# TestAdapter_02.net
KiCad netlist of a schematic drawn in EAGLE
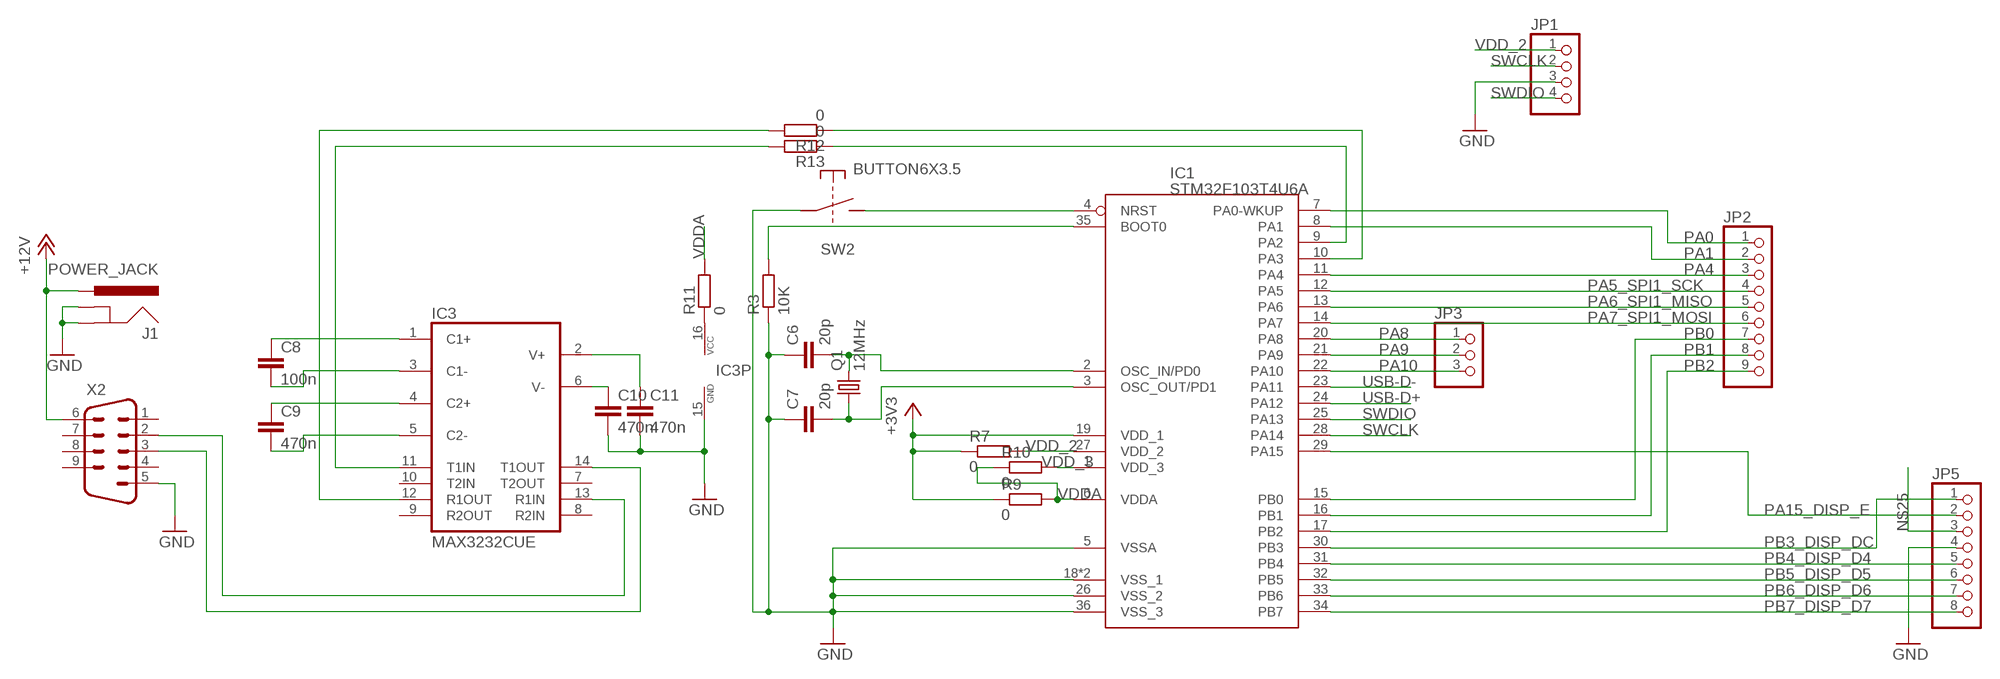
[diagram p0: schematic, sheet 1]
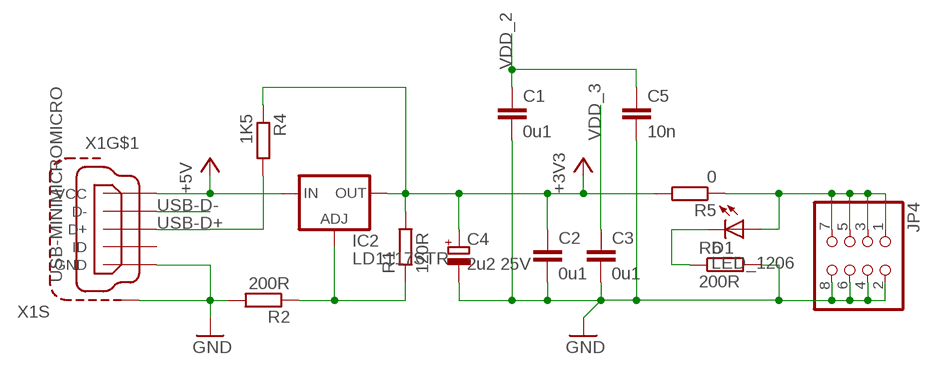
[diagram p1: schematic, sheet 2]

(export (version "E")
  (design (tool "Eeschema 10.0.6"))
  (components
    (comp (ref "C1")
      (value "0u1")
      (footprint "eagle-import:CAP0805")
      (libsource (lib "eagle-import") (part "CAP_0805"))
    )
    (comp (ref "C2")
      (value "0u1")
      (footprint "eagle-import:CAP0805")
      (libsource (lib "eagle-import") (part "CAP_0805"))
    )
    (comp (ref "C3")
      (value "0u1")
      (footprint "eagle-import:CAP0805")
      (libsource (lib "eagle-import") (part "CAP_0805"))
    )
    (comp (ref "C4")
      (value "2u2 25V")
      (footprint "eagle-import:CAPMP3317X180")
      (libsource (lib "eagle-import") (part "CAP-POL_CAPE3216-A"))
    )
    (comp (ref "C5")
      (value "10n")
      (footprint "eagle-import:CAP0805")
      (libsource (lib "eagle-import") (part "CAP_0805"))
    )
    (comp (ref "D1")
      (value "LED_1206")
      (footprint "eagle-import:LED1206")
      (libsource (lib "eagle-import") (part "LED_1206"))
    )
    (comp (ref "IC2")
      (value "LD1117STR")
      (footprint "eagle-import:SOT230P700X180-4")
      (libsource (lib "eagle-import") (part "VREG-ADJLD1117S"))
    )
    (comp (ref "JP4")
      (value "PINHD-2X4")
      (footprint "eagle-import:2X04")
      (libsource (lib "eagle-import") (part "PINHD-2X4"))
    )
    (comp (ref "R1")
      (value "120R")
      (footprint "eagle-import:RESC2012X50")
      (libsource (lib "eagle-import") (part "R_R0805"))
    )
    (comp (ref "R2")
      (value "200R")
      (footprint "eagle-import:RESC2012X50")
      (libsource (lib "eagle-import") (part "R_R0805"))
    )
    (comp (ref "R4")
      (value "1K5")
      (footprint "eagle-import:RESC2012X50")
      (libsource (lib "eagle-import") (part "R_R0805"))
    )
    (comp (ref "R5")
      (value "0")
      (footprint "eagle-import:RESC2012X50")
      (libsource (lib "eagle-import") (part "R_R0805"))
    )
    (comp (ref "R6")
      (value "200R")
      (footprint "eagle-import:RESC2012X50")
      (libsource (lib "eagle-import") (part "R_R0805"))
    )
    (comp (ref "X1")
      (value "USB-MINIMICROMICRO")
      (footprint "eagle-import:USB-B-MICRO-SMD")
      (libsource (lib "eagle-import") (part "USB-MINIMICROMICRO"))
    )
    (comp (ref "C6")
      (value "20p")
      (footprint "eagle-import:CAP0805")
      (libsource (lib "eagle-import") (part "CAP_0805"))
    )
    (comp (ref "C7")
      (value "20p")
      (footprint "eagle-import:CAP0805")
      (libsource (lib "eagle-import") (part "CAP_0805"))
    )
    (comp (ref "C8")
      (value "100n")
      (footprint "eagle-import:CAP0805")
      (libsource (lib "eagle-import") (part "CAP_0805"))
    )
    (comp (ref "C9")
      (value "470n")
      (footprint "eagle-import:CAP0805")
      (libsource (lib "eagle-import") (part "CAP_0805"))
    )
    (comp (ref "C10")
      (value "470n")
      (footprint "eagle-import:CAP0805")
      (libsource (lib "eagle-import") (part "CAP_0805"))
    )
    (comp (ref "C11")
      (value "470n")
      (footprint "eagle-import:CAP0805")
      (libsource (lib "eagle-import") (part "CAP_0805"))
    )
    (comp (ref "IC1")
      (value "STM32F103T4U6A")
      (footprint "eagle-import:QFN50P606X606X100-36")
      (libsource (lib "eagle-import") (part "STM32F103T4U6A"))
    )
    (comp (ref "IC3")
      (value "MAX3232CUE")
      (footprint "eagle-import:TSSOP16")
      (fields (field (name "MF") "MAXIM") (field (name "MPN") "MAX3232CUE+"))
      (libsource (lib "eagle-import") (part "MAX3232UEC"))
    )
    (comp (ref "J1")
      (value "POWER_JACK")
      (footprint "eagle-import:POWER_JACK_PTH")
      (libsource (lib "eagle-import") (part "POWER_JACK"))
    )
    (comp (ref "JP1")
      (value "PINHD-1X4")
      (footprint "eagle-import:1X04")
      (libsource (lib "eagle-import") (part "PINHD-1X4"))
    )
    (comp (ref "JP2")
      (value "PINHD-1X9")
      (footprint "eagle-import:1X09")
      (libsource (lib "eagle-import") (part "PINHD-1X9"))
    )
    (comp (ref "JP3")
      (value "PINHD-1X3")
      (footprint "eagle-import:1X03")
      (libsource (lib "eagle-import") (part "PINHD-1X3"))
    )
    (comp (ref "JP5")
      (value "PINHD-1X8")
      (footprint "eagle-import:1X08")
      (libsource (lib "eagle-import") (part "PINHD-1X8"))
    )
    (comp (ref "Q1")
      (value "12MHz")
      (footprint "eagle-import:CRYSTAL-5025")
      (libsource (lib "eagle-import") (part "CRYSTAL5032"))
    )
    (comp (ref "R3")
      (value "10K")
      (footprint "eagle-import:RESC2012X50")
      (libsource (lib "eagle-import") (part "R_R0805"))
    )
    (comp (ref "R7")
      (value "0")
      (footprint "eagle-import:RESC2012X50")
      (libsource (lib "eagle-import") (part "R_R0805"))
    )
    (comp (ref "R9")
      (value "0")
      (footprint "eagle-import:RESC2012X50")
      (libsource (lib "eagle-import") (part "R_R0805"))
    )
    (comp (ref "R10")
      (value "0")
      (footprint "eagle-import:RESC2012X50")
      (libsource (lib "eagle-import") (part "R_R0805"))
    )
    (comp (ref "R11")
      (value "0")
      (footprint "eagle-import:RESC2012X50")
      (libsource (lib "eagle-import") (part "R_R0805"))
    )
    (comp (ref "R12")
      (value "0")
      (footprint "eagle-import:RESC2012X50")
      (libsource (lib "eagle-import") (part "R_R0805"))
    )
    (comp (ref "R13")
      (value "0")
      (footprint "eagle-import:RESC2012X50")
      (libsource (lib "eagle-import") (part "R_R0805"))
    )
    (comp (ref "SW2")
      (value "BUTTON6X3.5")
      (footprint "eagle-import:SW-6X3.5")
      (libsource (lib "eagle-import") (part "BUTTON6X3.5"))
    )
    (comp (ref "X2")
      (value "M09-182")
      (footprint "eagle-import:182-009-MALE")
      (libsource (lib "eagle-import") (part "M09-182"))
    )
  )
  (nets
    (net (code "1") (name "+3V3") (class "Default")
      (node (ref "C2") (pin "1") (pinfunction "1_1") (pintype "passive"))
      (node (ref "C4") (pin "1") (pinfunction "+_1") (pintype "passive"))
      (node (ref "IC1") (pin "19") (pinfunction "VDD_1_19") (pintype "power_in"))
      (node (ref "IC2") (pin "2") (pinfunction "OUT_2") (pintype "passive"))
      (node (ref "IC2") (pin "4") (pinfunction "OUT_4") (pintype "passive"))
      (node (ref "R1") (pin "2") (pinfunction "2_2") (pintype "passive"))
      (node (ref "R4") (pin "1") (pinfunction "1_1") (pintype "passive"))
      (node (ref "R5") (pin "2") (pinfunction "2_2") (pintype "passive"))
      (node (ref "R7") (pin "1") (pinfunction "1_1") (pintype "passive"))
      (node (ref "R9") (pin "1") (pinfunction "1_1") (pintype "passive"))
    )
    (net (code "2") (name "+5V") (class "Default")
      (node (ref "IC2") (pin "3") (pinfunction "IN_3") (pintype "input"))
      (node (ref "X1") (pin "VBUS") (pinfunction "VCC_VBUS") (pintype "passive"))
    )
    (net (code "3") (name "+12V") (class "Default")
      (node (ref "J1") (pin "PWR") (pinfunction "PWR_PWR") (pintype "bidirectional"))
      (node (ref "X2") (pin "6") (pinfunction "6_6") (pintype "passive"))
    )
    (net (code "4") (name "GND") (class "Default")
      (node (ref "C1") (pin "2") (pinfunction "2_2") (pintype "passive"))
      (node (ref "C10") (pin "2") (pinfunction "2_2") (pintype "passive"))
      (node (ref "C11") (pin "2") (pinfunction "2_2") (pintype "passive"))
      (node (ref "C2") (pin "2") (pinfunction "2_2") (pintype "passive"))
      (node (ref "C3") (pin "2") (pinfunction "2_2") (pintype "passive"))
      (node (ref "C4") (pin "2") (pinfunction "-_2") (pintype "passive"))
      (node (ref "C5") (pin "2") (pinfunction "2_2") (pintype "passive"))
      (node (ref "C6") (pin "1") (pinfunction "1_1") (pintype "passive"))
      (node (ref "C7") (pin "1") (pinfunction "1_1") (pintype "passive"))
      (node (ref "IC1") (pin "18") (pinfunction "VSS_1_18") (pintype "power_in"))
      (node (ref "IC1") (pin "26") (pinfunction "VSS_2_26") (pintype "power_in"))
      (node (ref "IC1") (pin "36") (pinfunction "VSS_3_36") (pintype "power_in"))
      (node (ref "IC1") (pin "5") (pinfunction "VSSA_5") (pintype "power_in"))
      (node (ref "IC1") (pin "P$1") (pinfunction "VSS_1_P$1") (pintype "power_in"))
      (node (ref "IC3") (pin "15") (pinfunction "GND_15") (pintype "power_in"))
      (node (ref "J1") (pin "GND") (pinfunction "GND_GND") (pintype "bidirectional"))
      (node (ref "J1") (pin "GNDBREAK") (pinfunction "GNDBREAK_GNDBREAK") (pintype "bidirectional"))
      (node (ref "JP1") (pin "3") (pinfunction "3_3") (pintype "passive"))
      (node (ref "JP4") (pin "2") (pinfunction "2_2") (pintype "passive"))
      (node (ref "JP4") (pin "4") (pinfunction "4_4") (pintype "passive"))
      (node (ref "JP4") (pin "6") (pinfunction "6_6") (pintype "passive"))
      (node (ref "JP4") (pin "8") (pinfunction "8_8") (pintype "passive"))
      (node (ref "JP5") (pin "4") (pinfunction "4_4") (pintype "passive"))
      (node (ref "R2") (pin "2") (pinfunction "2_2") (pintype "passive"))
      (node (ref "R3") (pin "1") (pinfunction "1_1") (pintype "passive"))
      (node (ref "R6") (pin "2") (pinfunction "2_2") (pintype "passive"))
      (node (ref "SW2") (pin "1") (pinfunction "1_1") (pintype "passive"))
      (node (ref "X1") (pin "GND") (pinfunction "GND_GND") (pintype "passive"))
      (node (ref "X1") (pin "SHIELD1") (pinfunction "S1_SHIELD1") (pintype "passive"))
      (node (ref "X1") (pin "SHIELD2") (pinfunction "S1_SHIELD2") (pintype "passive"))
      (node (ref "X1") (pin "SHIELD3") (pinfunction "S1_SHIELD3") (pintype "passive"))
      (node (ref "X2") (pin "5") (pinfunction "5_5") (pintype "passive"))
    )
    (net (code "5") (name "N$25") (class "Default")
      (node (ref "D1") (pin "A") (pinfunction "A_A") (pintype "passive"))
      (node (ref "JP4") (pin "1") (pinfunction "1_1") (pintype "passive"))
      (node (ref "JP4") (pin "3") (pinfunction "3_3") (pintype "passive"))
      (node (ref "JP4") (pin "5") (pinfunction "5_5") (pintype "passive"))
      (node (ref "JP4") (pin "7") (pinfunction "7_7") (pintype "passive"))
      (node (ref "JP5") (pin "3") (pinfunction "3_3") (pintype "passive"))
      (node (ref "R5") (pin "1") (pinfunction "1_1") (pintype "passive"))
    )
    (net (code "6") (name "Net-(D1-PadC)") (class "Default")
      (node (ref "D1") (pin "C") (pinfunction "C_C") (pintype "passive"))
      (node (ref "R6") (pin "1") (pinfunction "1_1") (pintype "passive"))
    )
    (net (code "7") (name "Net-(IC1-BOOT0)") (class "Default")
      (node (ref "IC1") (pin "35") (pinfunction "BOOT0_35") (pintype "bidirectional"))
      (node (ref "R3") (pin "2") (pinfunction "2_2") (pintype "passive"))
    )
    (net (code "8") (name "Net-(IC1-NRST)") (class "Default")
      (node (ref "IC1") (pin "4") (pinfunction "NRST_4") (pintype "bidirectional"))
      (node (ref "SW2") (pin "2") (pinfunction "2_2") (pintype "passive"))
    )
    (net (code "9") (name "Net-(IC1-OSC_IN{slash}PD0)") (class "Default")
      (node (ref "C6") (pin "2") (pinfunction "2_2") (pintype "passive"))
      (node (ref "IC1") (pin "2") (pinfunction "OSC_IN/PD0_2") (pintype "bidirectional"))
      (node (ref "Q1") (pin "P$2") (pinfunction "2_P$2") (pintype "passive"))
    )
    (net (code "10") (name "Net-(IC1-OSC_OUT{slash}PD1)") (class "Default")
      (node (ref "C7") (pin "2") (pinfunction "2_2") (pintype "passive"))
      (node (ref "IC1") (pin "3") (pinfunction "OSC_OUT/PD1_3") (pintype "bidirectional"))
      (node (ref "Q1") (pin "P$1") (pinfunction "1_P$1") (pintype "passive"))
    )
    (net (code "11") (name "Net-(IC1-PA2)") (class "Default")
      (node (ref "IC1") (pin "9") (pinfunction "PA2_9") (pintype "bidirectional"))
      (node (ref "R13") (pin "1") (pinfunction "1_1") (pintype "passive"))
    )
    (net (code "12") (name "Net-(IC1-PA3)") (class "Default")
      (node (ref "IC1") (pin "10") (pinfunction "PA3_10") (pintype "bidirectional"))
      (node (ref "R12") (pin "1") (pinfunction "1_1") (pintype "passive"))
    )
    (net (code "13") (name "Net-(IC2-ADJ)") (class "Default")
      (node (ref "IC2") (pin "1") (pinfunction "ADJ_1") (pintype "input"))
      (node (ref "R1") (pin "1") (pinfunction "1_1") (pintype "passive"))
      (node (ref "R2") (pin "1") (pinfunction "1_1") (pintype "passive"))
    )
    (net (code "14") (name "Net-(IC3A-C1+)") (class "Default")
      (node (ref "C8") (pin "1") (pinfunction "1_1") (pintype "passive"))
      (node (ref "IC3") (pin "1") (pinfunction "C1+_1") (pintype "bidirectional"))
    )
    (net (code "15") (name "Net-(IC3A-C1-)") (class "Default")
      (node (ref "C8") (pin "2") (pinfunction "2_2") (pintype "passive"))
      (node (ref "IC3") (pin "3") (pinfunction "C1-_3") (pintype "bidirectional"))
    )
    (net (code "16") (name "Net-(IC3A-C2+)") (class "Default")
      (node (ref "C9") (pin "1") (pinfunction "1_1") (pintype "passive"))
      (node (ref "IC3") (pin "4") (pinfunction "C2+_4") (pintype "bidirectional"))
    )
    (net (code "17") (name "Net-(IC3A-C2-)") (class "Default")
      (node (ref "C9") (pin "2") (pinfunction "2_2") (pintype "passive"))
      (node (ref "IC3") (pin "5") (pinfunction "C2-_5") (pintype "bidirectional"))
    )
    (net (code "18") (name "Net-(IC3A-R1IN)") (class "Default")
      (node (ref "IC3") (pin "13") (pinfunction "R1IN_13") (pintype "input"))
      (node (ref "X2") (pin "2") (pinfunction "2_2") (pintype "passive"))
    )
    (net (code "19") (name "Net-(IC3A-R1OUT)") (class "Default")
      (node (ref "IC3") (pin "12") (pinfunction "R1OUT_12") (pintype "output"))
      (node (ref "R12") (pin "2") (pinfunction "2_2") (pintype "passive"))
    )
    (net (code "20") (name "Net-(IC3A-T1IN)") (class "Default")
      (node (ref "IC3") (pin "11") (pinfunction "T1IN_11") (pintype "input"))
      (node (ref "R13") (pin "2") (pinfunction "2_2") (pintype "passive"))
    )
    (net (code "21") (name "Net-(IC3A-T1OUT)") (class "Default")
      (node (ref "IC3") (pin "14") (pinfunction "T1OUT_14") (pintype "output"))
      (node (ref "X2") (pin "3") (pinfunction "3_3") (pintype "passive"))
    )
    (net (code "22") (name "Net-(IC3A-V+)") (class "Default")
      (node (ref "C11") (pin "1") (pinfunction "1_1") (pintype "passive"))
      (node (ref "IC3") (pin "2") (pinfunction "V+_2") (pintype "bidirectional"))
    )
    (net (code "23") (name "Net-(IC3A-V-)") (class "Default")
      (node (ref "C10") (pin "1") (pinfunction "1_1") (pintype "passive"))
      (node (ref "IC3") (pin "6") (pinfunction "V-_6") (pintype "bidirectional"))
    )
    (net (code "24") (name "Net-(IC3B-VCC)") (class "Default")
      (node (ref "IC3") (pin "16") (pinfunction "VCC_16") (pintype "power_in"))
      (node (ref "R11") (pin "1") (pinfunction "1_1") (pintype "passive"))
    )
    (net (code "25") (name "PA0") (class "Default")
      (node (ref "IC1") (pin "7") (pinfunction "PA0-WKUP_7") (pintype "bidirectional"))
      (node (ref "JP2") (pin "1") (pinfunction "1_1") (pintype "passive"))
    )
    (net (code "26") (name "PA1") (class "Default")
      (node (ref "IC1") (pin "8") (pinfunction "PA1_8") (pintype "bidirectional"))
      (node (ref "JP2") (pin "2") (pinfunction "2_2") (pintype "passive"))
    )
    (net (code "27") (name "PA4") (class "Default")
      (node (ref "IC1") (pin "11") (pinfunction "PA4_11") (pintype "bidirectional"))
      (node (ref "JP2") (pin "3") (pinfunction "3_3") (pintype "passive"))
    )
    (net (code "28") (name "PA5_SPI1_SCK") (class "Default")
      (node (ref "IC1") (pin "12") (pinfunction "PA5_12") (pintype "bidirectional"))
      (node (ref "JP2") (pin "4") (pinfunction "4_4") (pintype "passive"))
    )
    (net (code "29") (name "PA6_SPI1_MISO") (class "Default")
      (node (ref "IC1") (pin "13") (pinfunction "PA6_13") (pintype "bidirectional"))
      (node (ref "JP2") (pin "5") (pinfunction "5_5") (pintype "passive"))
    )
    (net (code "30") (name "PA7_SPI1_MOSI") (class "Default")
      (node (ref "IC1") (pin "14") (pinfunction "PA7_14") (pintype "bidirectional"))
      (node (ref "JP2") (pin "6") (pinfunction "6_6") (pintype "passive"))
    )
    (net (code "31") (name "PA8") (class "Default")
      (node (ref "IC1") (pin "20") (pinfunction "PA8_20") (pintype "bidirectional"))
      (node (ref "JP3") (pin "1") (pinfunction "1_1") (pintype "passive"))
    )
    (net (code "32") (name "PA9") (class "Default")
      (node (ref "IC1") (pin "21") (pinfunction "PA9_21") (pintype "bidirectional"))
      (node (ref "JP3") (pin "2") (pinfunction "2_2") (pintype "passive"))
    )
    (net (code "33") (name "PA10") (class "Default")
      (node (ref "IC1") (pin "22") (pinfunction "PA10_22") (pintype "bidirectional"))
      (node (ref "JP3") (pin "3") (pinfunction "3_3") (pintype "passive"))
    )
    (net (code "34") (name "PA15_DISP_E") (class "Default")
      (node (ref "IC1") (pin "29") (pinfunction "PA15_29") (pintype "bidirectional"))
      (node (ref "JP5") (pin "2") (pinfunction "2_2") (pintype "passive"))
    )
    (net (code "35") (name "PB0") (class "Default")
      (node (ref "IC1") (pin "15") (pinfunction "PB0_15") (pintype "bidirectional"))
      (node (ref "JP2") (pin "7") (pinfunction "7_7") (pintype "passive"))
    )
    (net (code "36") (name "PB1") (class "Default")
      (node (ref "IC1") (pin "16") (pinfunction "PB1_16") (pintype "bidirectional"))
      (node (ref "JP2") (pin "8") (pinfunction "8_8") (pintype "passive"))
    )
    (net (code "37") (name "PB2") (class "Default")
      (node (ref "IC1") (pin "17") (pinfunction "PB2_17") (pintype "bidirectional"))
      (node (ref "JP2") (pin "9") (pinfunction "9_9") (pintype "passive"))
    )
    (net (code "38") (name "PB3_DISP_DC") (class "Default")
      (node (ref "IC1") (pin "30") (pinfunction "PB3_30") (pintype "bidirectional"))
      (node (ref "JP5") (pin "1") (pinfunction "1_1") (pintype "passive"))
    )
    (net (code "39") (name "PB4_DISP_D4") (class "Default")
      (node (ref "IC1") (pin "31") (pinfunction "PB4_31") (pintype "bidirectional"))
      (node (ref "JP5") (pin "5") (pinfunction "5_5") (pintype "passive"))
    )
    (net (code "40") (name "PB5_DISP_D5") (class "Default")
      (node (ref "IC1") (pin "32") (pinfunction "PB5_32") (pintype "bidirectional"))
      (node (ref "JP5") (pin "6") (pinfunction "6_6") (pintype "passive"))
    )
    (net (code "41") (name "PB6_DISP_D6") (class "Default")
      (node (ref "IC1") (pin "33") (pinfunction "PB6_33") (pintype "bidirectional"))
      (node (ref "JP5") (pin "7") (pinfunction "7_7") (pintype "passive"))
    )
    (net (code "42") (name "PB7_DISP_D7") (class "Default")
      (node (ref "IC1") (pin "34") (pinfunction "PB7_34") (pintype "bidirectional"))
      (node (ref "JP5") (pin "8") (pinfunction "8_8") (pintype "passive"))
    )
    (net (code "43") (name "SWCLK") (class "Default")
      (node (ref "IC1") (pin "28") (pinfunction "PA14_28") (pintype "bidirectional"))
      (node (ref "JP1") (pin "2") (pinfunction "2_2") (pintype "passive"))
    )
    (net (code "44") (name "SWDIO") (class "Default")
      (node (ref "IC1") (pin "25") (pinfunction "PA13_25") (pintype "bidirectional"))
      (node (ref "JP1") (pin "4") (pinfunction "4_4") (pintype "passive"))
    )
    (net (code "45") (name "USB-D+") (class "Default")
      (node (ref "IC1") (pin "24") (pinfunction "PA12_24") (pintype "bidirectional"))
      (node (ref "R4") (pin "2") (pinfunction "2_2") (pintype "passive"))
      (node (ref "X1") (pin "D+") (pinfunction "D+_D+") (pintype "passive"))
    )
    (net (code "46") (name "USB-D-") (class "Default")
      (node (ref "IC1") (pin "23") (pinfunction "PA11_23") (pintype "bidirectional"))
      (node (ref "X1") (pin "D-") (pinfunction "D-_D-") (pintype "passive"))
    )
    (net (code "47") (name "VDDA") (class "Default")
      (node (ref "IC1") (pin "6") (pinfunction "VDDA_6") (pintype "power_in"))
      (node (ref "R10") (pin "1") (pinfunction "1_1") (pintype "passive"))
      (node (ref "R11") (pin "2") (pinfunction "2_2") (pintype "passive"))
      (node (ref "R9") (pin "2") (pinfunction "2_2") (pintype "passive"))
    )
    (net (code "48") (name "VDD_2") (class "Default")
      (node (ref "C1") (pin "1") (pinfunction "1_1") (pintype "passive"))
      (node (ref "C5") (pin "1") (pinfunction "1_1") (pintype "passive"))
      (node (ref "IC1") (pin "27") (pinfunction "VDD_2_27") (pintype "power_in"))
      (node (ref "JP1") (pin "1") (pinfunction "1_1") (pintype "passive"))
      (node (ref "R7") (pin "2") (pinfunction "2_2") (pintype "passive"))
    )
    (net (code "49") (name "VDD_3") (class "Default")
      (node (ref "C3") (pin "1") (pinfunction "1_1") (pintype "passive"))
      (node (ref "IC1") (pin "1") (pinfunction "VDD_3_1") (pintype "power_in"))
      (node (ref "R10") (pin "2") (pinfunction "2_2") (pintype "passive"))
    )
    (net (code "50") (name "unconnected-(IC3A-R2IN-Pad8)") (class "Default")
      (node (ref "IC3") (pin "8") (pinfunction "R2IN_8") (pintype "input"))
    )
    (net (code "51") (name "unconnected-(IC3A-R2OUT-Pad9)") (class "Default")
      (node (ref "IC3") (pin "9") (pinfunction "R2OUT_9") (pintype "output"))
    )
    (net (code "52") (name "unconnected-(IC3A-T2IN-Pad10)") (class "Default")
      (node (ref "IC3") (pin "10") (pinfunction "T2IN_10") (pintype "input"))
    )
    (net (code "53") (name "unconnected-(IC3A-T2OUT-Pad7)") (class "Default")
      (node (ref "IC3") (pin "7") (pinfunction "T2OUT_7") (pintype "output"))
    )
    (net (code "54") (name "unconnected-(X1-PadID)") (class "Default")
      (node (ref "X1") (pin "ID") (pinfunction "ID_ID") (pintype "passive"))
    )
    (net (code "55") (name "unconnected-(X2-Pad1)") (class "Default")
      (node (ref "X2") (pin "1") (pinfunction "1_1") (pintype "passive"))
    )
    (net (code "56") (name "unconnected-(X2-Pad4)") (class "Default")
      (node (ref "X2") (pin "4") (pinfunction "4_4") (pintype "passive"))
    )
    (net (code "57") (name "unconnected-(X2-Pad7)") (class "Default")
      (node (ref "X2") (pin "7") (pinfunction "7_7") (pintype "passive"))
    )
    (net (code "58") (name "unconnected-(X2-Pad8)") (class "Default")
      (node (ref "X2") (pin "8") (pinfunction "8_8") (pintype "passive"))
    )
    (net (code "59") (name "unconnected-(X2-Pad9)") (class "Default")
      (node (ref "X2") (pin "9") (pinfunction "9_9") (pintype "passive"))
    )
  )
)
